# MIDI_ID.net
KiCad netlist of a schematic drawn in Altium Designer
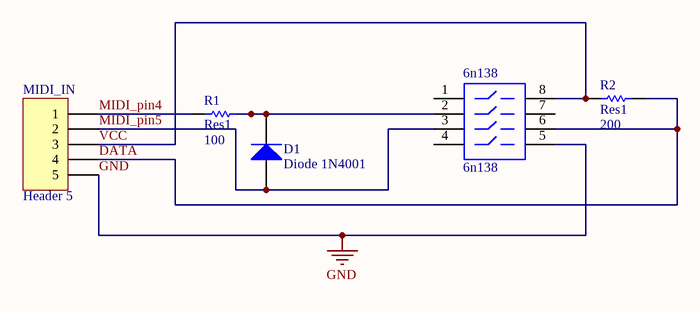
[diagram p0: MIDI_ID.SchDoc]

(export (version "E")
  (design (tool "Eeschema 10.0.6"))
  (components
    (comp (ref "6n138")
      (value "6n138")
      (footprint "DIP-8")
      (fields (field (name "PUBLISHER") "Altium Limited"))
      (libsource (lib "Miscellaneous Devices") (part "SW-DIP4"))
    )
    (comp (ref "D1")
      (value "Diode 1N4001")
      (footprint "DO-41")
      (description "1 Amp General Purpose Rectifier")
      (fields (field (name "PUBLISHER") "Altium Limited"))
      (libsource (lib "Miscellaneous Devices") (part "Diode 1N4001"))
    )
    (comp (ref "MIDI_IN")
      (value "Header 5")
      (footprint "HDR1X5")
      (description "Header, 5-Pin")
      (fields (field (name "PUBLISHER") "Altium Limited"))
      (libsource (lib "Miscellaneous Connectors") (part "Header 5"))
    )
    (comp (ref "R1")
      (value "Res1")
      (footprint "AXIAL-0.3")
      (description "Resistor")
      (fields (field (name "ALTIUM_VALUE") "100") (field (name "PUBLISHER") "Altium Limited"))
      (libsource (lib "Miscellaneous Devices") (part "Res1"))
    )
    (comp (ref "R2")
      (value "Res1")
      (footprint "AXIAL-0.3")
      (description "Resistor")
      (fields (field (name "ALTIUM_VALUE") "200") (field (name "PUBLISHER") "Altium Limited"))
      (libsource (lib "Miscellaneous Devices") (part "Res1"))
    )
  )
  (nets
    (net (code "1") (name "/DATA") (class "Default")
      (node (ref "6n138") (pin "6") (pinfunction "6_6") (pintype "passive"))
      (node (ref "MIDI_IN") (pin "4") (pinfunction "4_4") (pintype "passive"))
      (node (ref "R2") (pin "2") (pinfunction "2_2") (pintype "passive"))
    )
    (net (code "2") (name "/MIDI_pin4") (class "Default")
      (node (ref "MIDI_IN") (pin "1") (pinfunction "1_1") (pintype "passive"))
      (node (ref "R1") (pin "1") (pinfunction "1_1") (pintype "passive"))
    )
    (net (code "3") (name "/MIDI_pin5") (class "Default")
      (node (ref "6n138") (pin "3") (pinfunction "3_3") (pintype "passive"))
      (node (ref "D1") (pin "1") (pinfunction "A_1") (pintype "passive"))
      (node (ref "MIDI_IN") (pin "2") (pinfunction "2_2") (pintype "passive"))
    )
    (net (code "4") (name "/VCC") (class "Default")
      (node (ref "6n138") (pin "8") (pinfunction "8_8") (pintype "passive"))
      (node (ref "MIDI_IN") (pin "3") (pinfunction "3_3") (pintype "passive"))
      (node (ref "R2") (pin "1") (pinfunction "1_1") (pintype "passive"))
    )
    (net (code "5") (name "GND") (class "Default")
      (node (ref "6n138") (pin "5") (pinfunction "5_5") (pintype "passive"))
      (node (ref "MIDI_IN") (pin "5") (pinfunction "5_5") (pintype "passive"))
    )
    (net (code "6") (name "Net-(D1-K)") (class "Default")
      (node (ref "6n138") (pin "2") (pinfunction "2_2") (pintype "passive"))
      (node (ref "D1") (pin "2") (pinfunction "K_2") (pintype "passive"))
      (node (ref "R1") (pin "2") (pinfunction "2_2") (pintype "passive"))
    )
    (net (code "7") (name "unconnected-(6n138-Pad1)") (class "Default")
      (node (ref "6n138") (pin "1") (pinfunction "1_1") (pintype "passive"))
    )
    (net (code "8") (name "unconnected-(6n138-Pad4)") (class "Default")
      (node (ref "6n138") (pin "4") (pinfunction "4_4") (pintype "passive"))
    )
    (net (code "9") (name "unconnected-(6n138-Pad7)") (class "Default")
      (node (ref "6n138") (pin "7") (pinfunction "7_7") (pintype "passive"))
    )
  )
)
